# hybrid.net
KiCad netlist of a schematic drawn in EAGLE
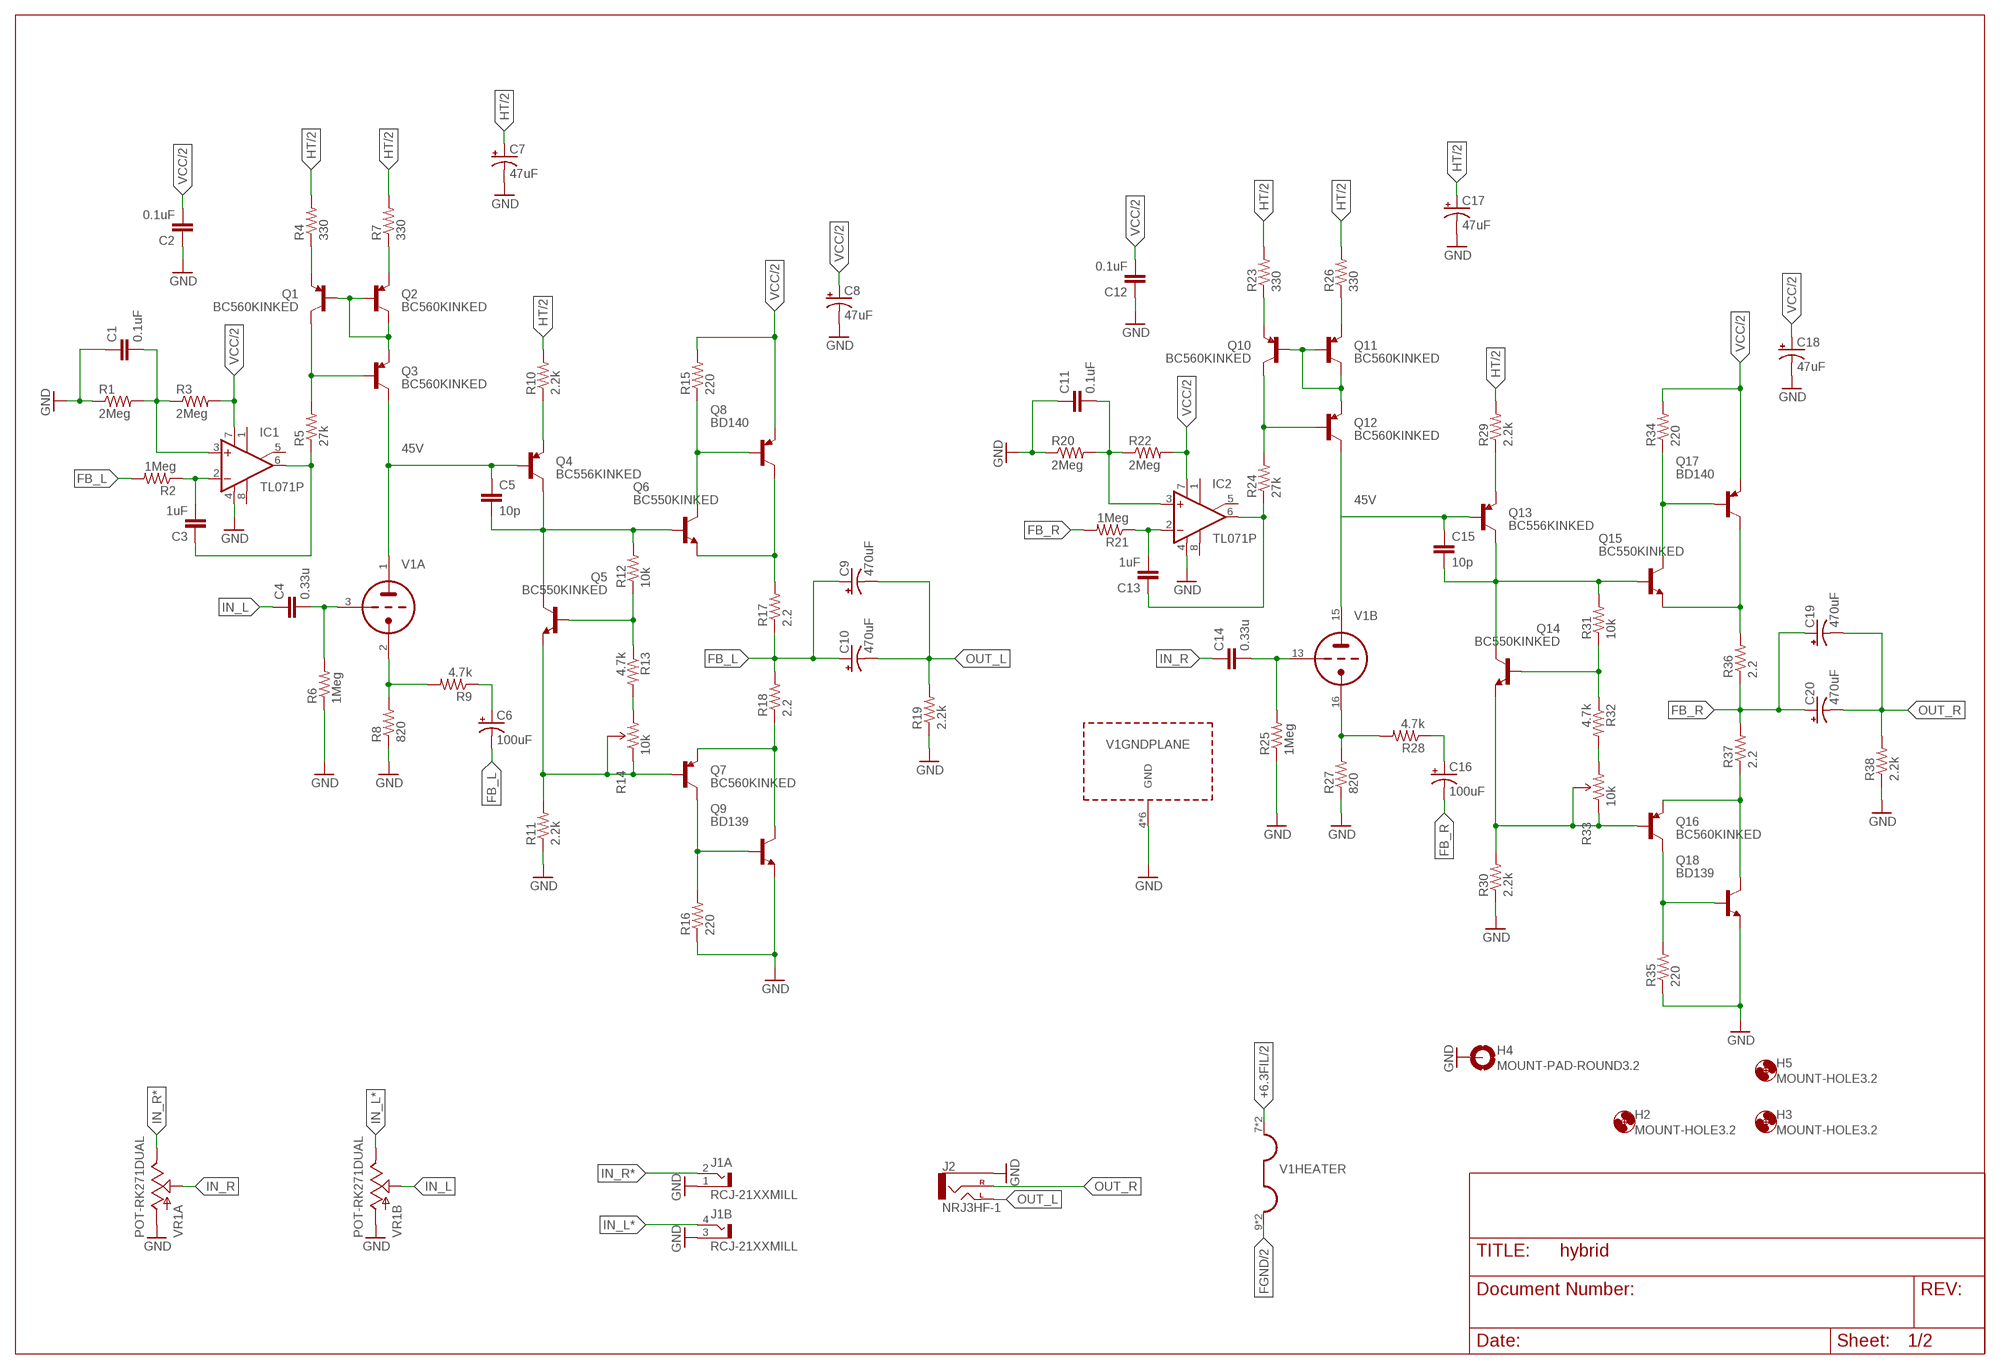
[diagram p0: schematic, sheet 1]
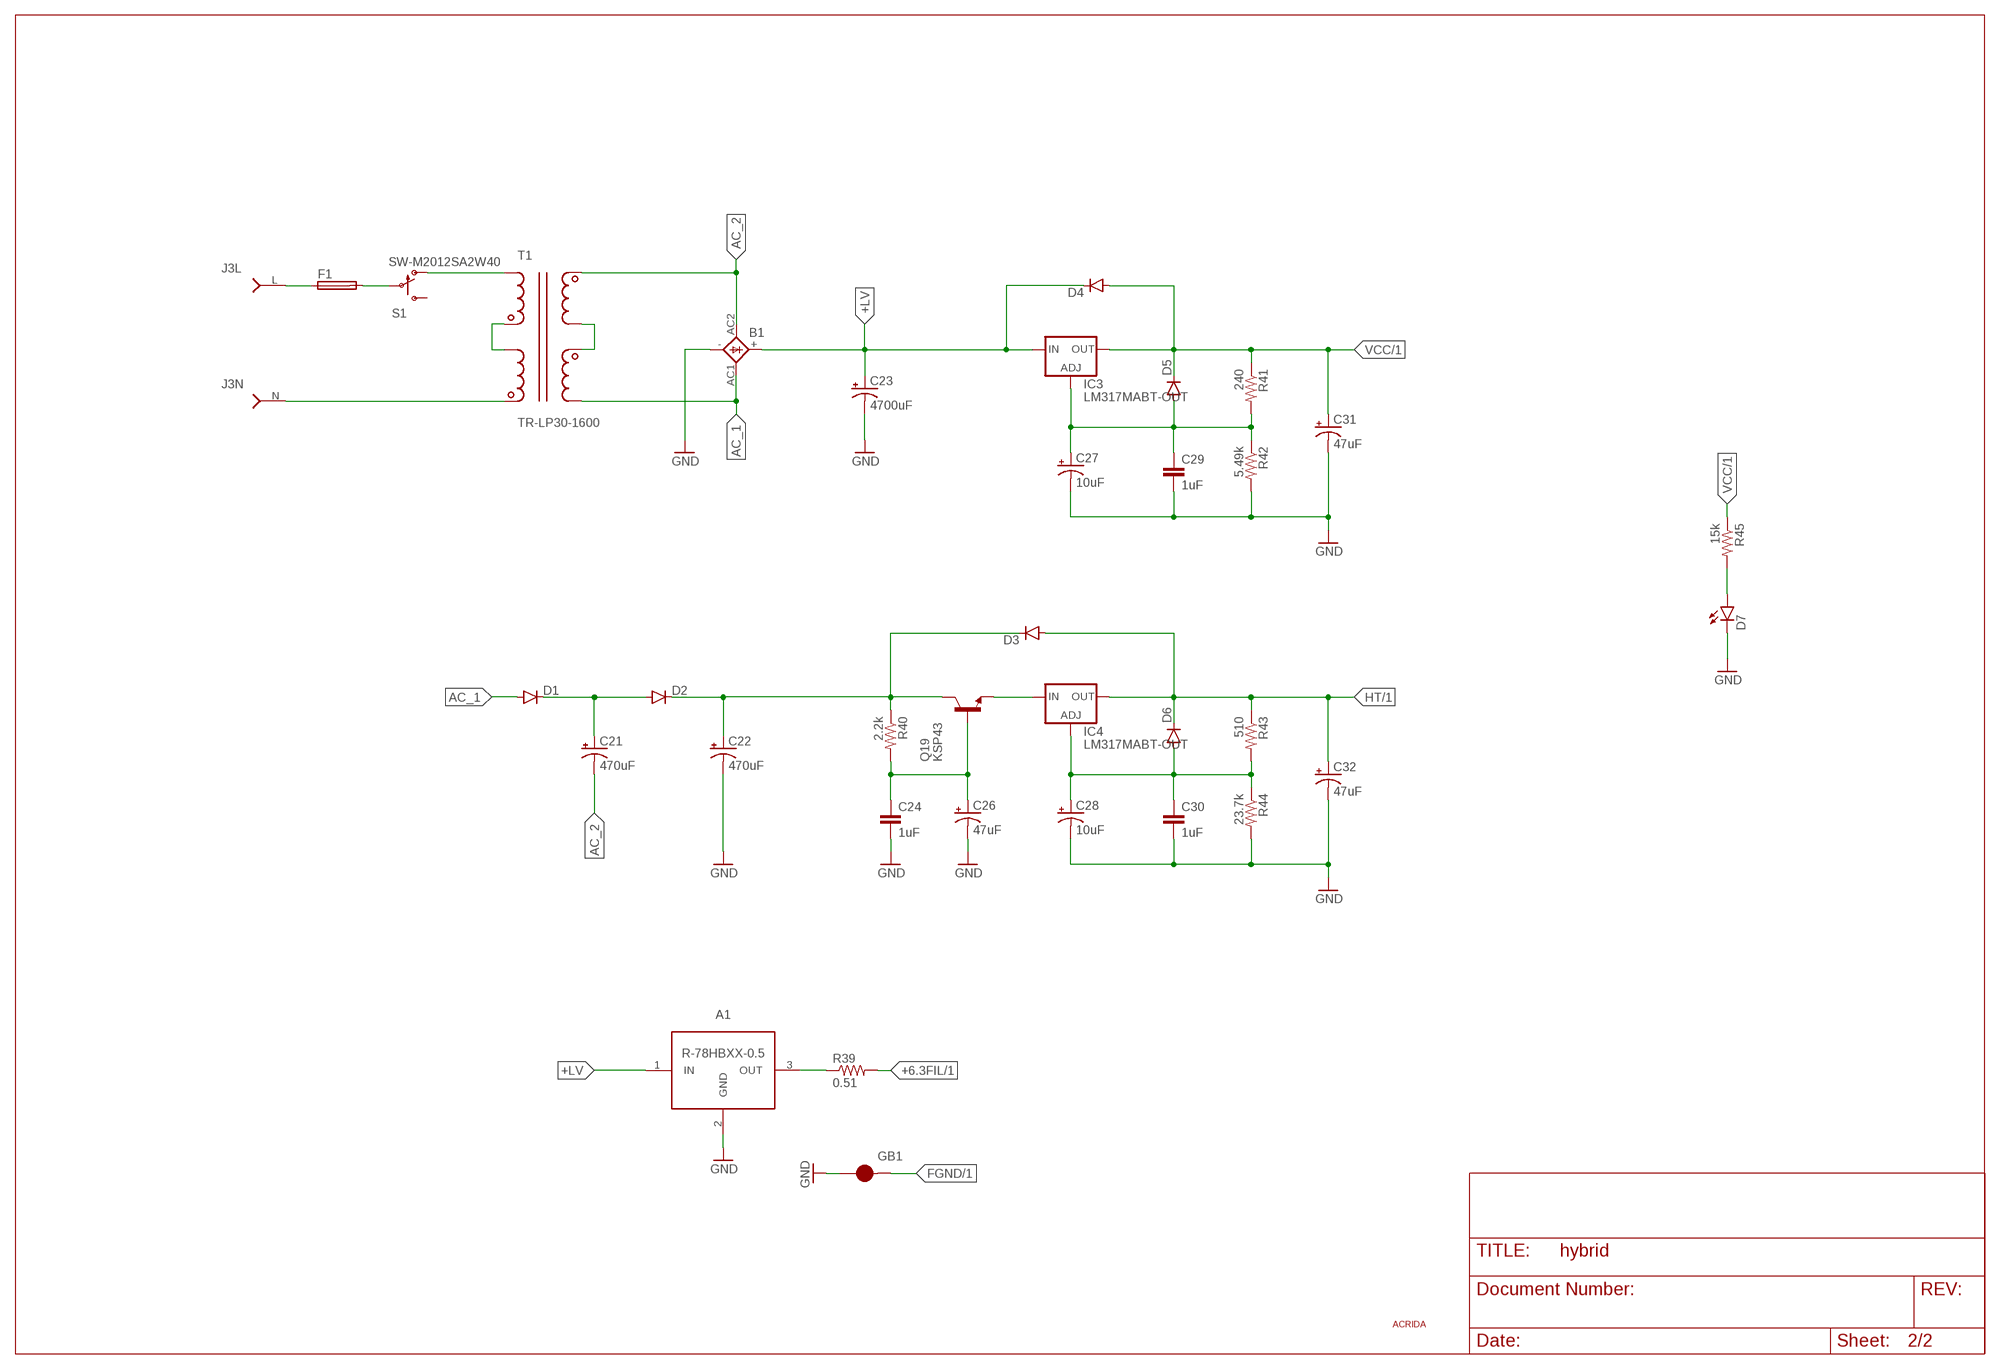
[diagram p1: schematic, sheet 2]

(export (version "E")
  (design (tool "Eeschema 10.0.6"))
  (components
    (comp (ref "A1")
      (value "R-78HBXX-0.5")
      (footprint "eagle-import:R-78HB")
      (libsource (lib "eagle-import") (part "R-78HBXX-0.5"))
    )
    (comp (ref "B1")
      (value "GBU4")
      (footprint "eagle-import:GBU4S")
      (libsource (lib "eagle-import") (part "GBU4"))
    )
    (comp (ref "C21")
      (value "470uF")
      (footprint "eagle-import:CPOL-RADIAL-18_7.5")
      (libsource (lib "eagle-import") (part "CAP_POLPTH-18/7.5"))
    )
    (comp (ref "C22")
      (value "470uF")
      (footprint "eagle-import:CPOL-RADIAL-18_7.5")
      (libsource (lib "eagle-import") (part "CAP_POLPTH-18/7.5"))
    )
    (comp (ref "C23")
      (value "4700uF")
      (footprint "eagle-import:CPOL-SNAPIN-30_10")
      (libsource (lib "eagle-import") (part "CAP_POLSNAPIN-30/10"))
    )
    (comp (ref "C24")
      (value "1uF")
      (footprint "eagle-import:CAP-PTH-SMALL")
      (libsource (lib "eagle-import") (part "CAPPTH"))
    )
    (comp (ref "C26")
      (value "47uF")
      (footprint "eagle-import:CPOL-RADIAL-12_5")
      (libsource (lib "eagle-import") (part "CAP_POLPTH-12/5"))
    )
    (comp (ref "C27")
      (value "10uF")
      (footprint "eagle-import:CPOL-RADIAL-5_2.5")
      (libsource (lib "eagle-import") (part "CAP_POLPTH-5/2.5"))
    )
    (comp (ref "C28")
      (value "10uF")
      (footprint "eagle-import:CPOL-RADIAL-6.5_2.5")
      (libsource (lib "eagle-import") (part "CAP_POLPTH-6.5/2.5"))
    )
    (comp (ref "C29")
      (value "1uF")
      (footprint "eagle-import:CAP-PTH-SMALL")
      (libsource (lib "eagle-import") (part "CAPPTH"))
    )
    (comp (ref "C30")
      (value "1uF")
      (footprint "eagle-import:CAP-PTH-SMALL")
      (libsource (lib "eagle-import") (part "CAPPTH"))
    )
    (comp (ref "C31")
      (value "47uF")
      (footprint "eagle-import:CPOL-RADIAL-8_3.5")
      (libsource (lib "eagle-import") (part "CAP_POLPTH-8/3.5"))
    )
    (comp (ref "C32")
      (value "47uF")
      (footprint "eagle-import:CPOL-RADIAL-8_3.5")
      (libsource (lib "eagle-import") (part "CAP_POLPTH-8/3.5"))
    )
    (comp (ref "D1")
      (value "DIODEPTH")
      (footprint "eagle-import:DIODE-1N4001")
      (libsource (lib "eagle-import") (part "DIODEPTH"))
    )
    (comp (ref "D2")
      (value "DIODEPTH")
      (footprint "eagle-import:DIODE-1N4001")
      (libsource (lib "eagle-import") (part "DIODEPTH"))
    )
    (comp (ref "D3")
      (value "DIODEPTH")
      (footprint "eagle-import:DIODE-1N4001")
      (libsource (lib "eagle-import") (part "DIODEPTH"))
    )
    (comp (ref "D4")
      (value "DIODEPTH")
      (footprint "eagle-import:DIODE-1N4001")
      (libsource (lib "eagle-import") (part "DIODEPTH"))
    )
    (comp (ref "D5")
      (value "DIODEPTH")
      (footprint "eagle-import:DIODE-1N4001")
      (libsource (lib "eagle-import") (part "DIODEPTH"))
    )
    (comp (ref "D6")
      (value "DIODEPTH")
      (footprint "eagle-import:DIODE-1N4001")
      (libsource (lib "eagle-import") (part "DIODEPTH"))
    )
    (comp (ref "D7")
      (value "LED3MM")
      (footprint "eagle-import:LED3MM")
      (libsource (lib "eagle-import") (part "LED3MM"))
    )
    (comp (ref "F1")
      (value "SH22,5")
      (footprint "eagle-import:SH22,5")
      (fields (field (name "MF") "SCHURTER") (field (name "MPN") "0031.8201"))
      (libsource (lib "eagle-import") (part "SH22,5"))
    )
    (comp (ref "GB1")
      (value "COPPER-BRIDGESM")
      (footprint "eagle-import:COPPER-BRIDGE-SM")
      (libsource (lib "eagle-import") (part "COPPER-BRIDGESM"))
    )
    (comp (ref "IC3")
      (value "LM317MABT-OUT")
      (footprint "eagle-import:TO220L1-OUT")
      (libsource (lib "eagle-import") (part "LM317?MABT-OUT"))
    )
    (comp (ref "IC4")
      (value "LM317MABT-OUT")
      (footprint "eagle-import:TO220L1-OUT")
      (libsource (lib "eagle-import") (part "LM317?MABT-OUT"))
    )
    (comp (ref "J3")
      (value "703W-00/54")
      (footprint "eagle-import:703W-00_54")
      (libsource (lib "eagle-import") (part "703W-00/54"))
    )
    (comp (ref "Q19")
      (value "KSP43")
      (footprint "eagle-import:TO-92")
      (libsource (lib "eagle-import") (part "KSP43"))
    )
    (comp (ref "R39")
      (value "0.51")
      (footprint "eagle-import:AXIAL-0.5")
      (libsource (lib "eagle-import") (part "my-res_RESISTORPTH-1/2W"))
    )
    (comp (ref "R40")
      (value "2.2k")
      (footprint "eagle-import:AXIAL-0.4")
      (libsource (lib "eagle-import") (part "RESISTORPTH-1/4W"))
    )
    (comp (ref "R41")
      (value "240")
      (footprint "eagle-import:AXIAL-0.4")
      (libsource (lib "eagle-import") (part "RESISTORPTH-1/4W"))
    )
    (comp (ref "R42")
      (value "5.49k")
      (footprint "eagle-import:AXIAL-0.4")
      (libsource (lib "eagle-import") (part "RESISTORPTH-1/4W"))
    )
    (comp (ref "R43")
      (value "510")
      (footprint "eagle-import:AXIAL-0.4")
      (libsource (lib "eagle-import") (part "RESISTORPTH-1/4W"))
    )
    (comp (ref "R44")
      (value "23.7k")
      (footprint "eagle-import:AXIAL-0.4")
      (libsource (lib "eagle-import") (part "RESISTORPTH-1/4W"))
    )
    (comp (ref "R45")
      (value "15k")
      (footprint "eagle-import:AXIAL-0.4")
      (libsource (lib "eagle-import") (part "RESISTORPTH-1/4W"))
    )
    (comp (ref "S1")
      (value "SW-M2012SA2W40")
      (footprint "eagle-import:SW-M2012S2A2G40")
      (libsource (lib "eagle-import") (part "SW-M2012SA2W40"))
    )
    (comp (ref "T1")
      (value "TR-LP30-1600")
      (footprint "eagle-import:TR-LP30-1600")
      (libsource (lib "eagle-import") (part "TR-LP30-1600"))
    )
    (comp (ref "U$1")
      (value "ACRIDA-LOGO")
      (footprint "eagle-import:ACRIDA-LOGO")
      (libsource (lib "eagle-import") (part "ACRIDA-LOGO"))
    )
    (comp (ref "C1")
      (value "0.1uF")
      (footprint "eagle-import:CAP-PTH-SMALL")
      (libsource (lib "eagle-import") (part "CAPPTH"))
    )
    (comp (ref "C2")
      (value "0.1uF")
      (footprint "eagle-import:CAP-PTH-SMALL")
      (libsource (lib "eagle-import") (part "CAPPTH"))
    )
    (comp (ref "C3")
      (value "1uF")
      (footprint "eagle-import:C5B5")
      (libsource (lib "eagle-import") (part "C5/5"))
    )
    (comp (ref "C4")
      (value "0.33u")
      (footprint "eagle-import:C5B3.5")
      (libsource (lib "eagle-import") (part "C5/3.5"))
    )
    (comp (ref "C5")
      (value "10p")
      (footprint "eagle-import:CAP-PTH-SMALL")
      (libsource (lib "eagle-import") (part "CAPPTH"))
    )
    (comp (ref "C6")
      (value "100uF")
      (footprint "eagle-import:CPOL-RADIAL-8_3.5")
      (libsource (lib "eagle-import") (part "CAP_POLPTH-8/3.5"))
    )
    (comp (ref "C7")
      (value "47uF")
      (footprint "eagle-import:CPOL-RADIAL-8_3.5")
      (libsource (lib "eagle-import") (part "CAP_POLPTH-8/3.5"))
    )
    (comp (ref "C8")
      (value "47uF")
      (footprint "eagle-import:CPOL-RADIAL-8_3.5")
      (libsource (lib "eagle-import") (part "CAP_POLPTH-8/3.5"))
    )
    (comp (ref "C9")
      (value "470uF")
      (footprint "eagle-import:CPOL-RADIAL-12.5_5")
      (libsource (lib "eagle-import") (part "CAP_POLPTH-12.5/5"))
    )
    (comp (ref "C10")
      (value "470uF")
      (footprint "eagle-import:CPOL-RADIAL-12.5_5")
      (libsource (lib "eagle-import") (part "CAP_POLPTH-12.5/5"))
    )
    (comp (ref "C11")
      (value "0.1uF")
      (footprint "eagle-import:CAP-PTH-SMALL")
      (libsource (lib "eagle-import") (part "CAPPTH"))
    )
    (comp (ref "C12")
      (value "0.1uF")
      (footprint "eagle-import:CAP-PTH-SMALL")
      (libsource (lib "eagle-import") (part "CAPPTH"))
    )
    (comp (ref "C13")
      (value "1uF")
      (footprint "eagle-import:C5B5")
      (libsource (lib "eagle-import") (part "C5/5"))
    )
    (comp (ref "C14")
      (value "0.33u")
      (footprint "eagle-import:C5B3.5")
      (libsource (lib "eagle-import") (part "C5/3.5"))
    )
    (comp (ref "C15")
      (value "10p")
      (footprint "eagle-import:CAP-PTH-SMALL")
      (libsource (lib "eagle-import") (part "CAPPTH"))
    )
    (comp (ref "C16")
      (value "100uF")
      (footprint "eagle-import:CPOL-RADIAL-8_3.5")
      (libsource (lib "eagle-import") (part "CAP_POLPTH-8/3.5"))
    )
    (comp (ref "C17")
      (value "47uF")
      (footprint "eagle-import:CPOL-RADIAL-8_3.5")
      (libsource (lib "eagle-import") (part "CAP_POLPTH-8/3.5"))
    )
    (comp (ref "C18")
      (value "47uF")
      (footprint "eagle-import:CPOL-RADIAL-8_3.5")
      (libsource (lib "eagle-import") (part "CAP_POLPTH-8/3.5"))
    )
    (comp (ref "C19")
      (value "470uF")
      (footprint "eagle-import:CPOL-RADIAL-12.5_5")
      (libsource (lib "eagle-import") (part "CAP_POLPTH-12.5/5"))
    )
    (comp (ref "C20")
      (value "470uF")
      (footprint "eagle-import:CPOL-RADIAL-12.5_5")
      (libsource (lib "eagle-import") (part "CAP_POLPTH-12.5/5"))
    )
    (comp (ref "H2")
      (value "MOUNT-HOLE3.2")
      (footprint "eagle-import:3,2")
      (libsource (lib "eagle-import") (part "MOUNT-HOLE3.2"))
    )
    (comp (ref "H3")
      (value "MOUNT-HOLE3.2")
      (footprint "eagle-import:3,2")
      (libsource (lib "eagle-import") (part "MOUNT-HOLE3.2"))
    )
    (comp (ref "H4")
      (value "MOUNT-PAD-ROUND3.2")
      (footprint "eagle-import:3,2-PAD")
      (libsource (lib "eagle-import") (part "MOUNT-PAD-ROUND3.2"))
    )
    (comp (ref "H5")
      (value "MOUNT-HOLE3.2")
      (footprint "eagle-import:3,2")
      (libsource (lib "eagle-import") (part "MOUNT-HOLE3.2"))
    )
    (comp (ref "IC1")
      (value "TL071P")
      (footprint "eagle-import:DIL08")
      (libsource (lib "eagle-import") (part "TL071P"))
    )
    (comp (ref "IC2")
      (value "TL071P")
      (footprint "eagle-import:DIL08")
      (libsource (lib "eagle-import") (part "TL071P"))
    )
    (comp (ref "J1")
      (value "RCJ-21XXMILL")
      (footprint "eagle-import:RCJ-21-MILL")
      (libsource (lib "eagle-import") (part "RCJ-21XXMILL"))
    )
    (comp (ref "J2")
      (value "NRJ3HF-1")
      (footprint "eagle-import:NRJ3HF")
      (libsource (lib "eagle-import") (part "NRJ3HF-1"))
    )
    (comp (ref "Q1")
      (value "BC560KINKED")
      (footprint "eagle-import:TO92-BENT")
      (libsource (lib "eagle-import") (part "BC560KINKED"))
    )
    (comp (ref "Q2")
      (value "BC560KINKED")
      (footprint "eagle-import:TO92-BENT")
      (libsource (lib "eagle-import") (part "BC560KINKED"))
    )
    (comp (ref "Q3")
      (value "BC560KINKED")
      (footprint "eagle-import:TO92-BENT")
      (libsource (lib "eagle-import") (part "BC560KINKED"))
    )
    (comp (ref "Q4")
      (value "BC556KINKED")
      (footprint "eagle-import:TO92-BENT")
      (libsource (lib "eagle-import") (part "BC556KINKED"))
    )
    (comp (ref "Q5")
      (value "BC550KINKED")
      (footprint "eagle-import:TO92-BENT")
      (libsource (lib "eagle-import") (part "BC550KINKED"))
    )
    (comp (ref "Q6")
      (value "BC550KINKED")
      (footprint "eagle-import:TO92-BENT")
      (libsource (lib "eagle-import") (part "BC550KINKED"))
    )
    (comp (ref "Q7")
      (value "BC560KINKED")
      (footprint "eagle-import:TO92-BENT")
      (libsource (lib "eagle-import") (part "BC560KINKED"))
    )
    (comp (ref "Q8")
      (value "BD140")
      (footprint "eagle-import:TO126")
      (libsource (lib "eagle-import") (part "BD140"))
    )
    (comp (ref "Q9")
      (value "BD139")
      (footprint "eagle-import:TO126")
      (libsource (lib "eagle-import") (part "BD139"))
    )
    (comp (ref "Q10")
      (value "BC560KINKED")
      (footprint "eagle-import:TO92-BENT")
      (libsource (lib "eagle-import") (part "BC560KINKED"))
    )
    (comp (ref "Q11")
      (value "BC560KINKED")
      (footprint "eagle-import:TO92-BENT")
      (libsource (lib "eagle-import") (part "BC560KINKED"))
    )
    (comp (ref "Q12")
      (value "BC560KINKED")
      (footprint "eagle-import:TO92-BENT")
      (libsource (lib "eagle-import") (part "BC560KINKED"))
    )
    (comp (ref "Q13")
      (value "BC556KINKED")
      (footprint "eagle-import:TO92-BENT")
      (libsource (lib "eagle-import") (part "BC556KINKED"))
    )
    (comp (ref "Q14")
      (value "BC550KINKED")
      (footprint "eagle-import:TO92-BENT")
      (libsource (lib "eagle-import") (part "BC550KINKED"))
    )
    (comp (ref "Q15")
      (value "BC550KINKED")
      (footprint "eagle-import:TO92-BENT")
      (libsource (lib "eagle-import") (part "BC550KINKED"))
    )
    (comp (ref "Q16")
      (value "BC560KINKED")
      (footprint "eagle-import:TO92-BENT")
      (libsource (lib "eagle-import") (part "BC560KINKED"))
    )
    (comp (ref "Q17")
      (value "BD140")
      (footprint "eagle-import:TO126")
      (libsource (lib "eagle-import") (part "BD140"))
    )
    (comp (ref "Q18")
      (value "BD139")
      (footprint "eagle-import:TO126")
      (libsource (lib "eagle-import") (part "BD139"))
    )
    (comp (ref "R1")
      (value "2Meg")
      (footprint "eagle-import:AXIAL-0.4")
      (libsource (lib "eagle-import") (part "RESISTORPTH-1/4W"))
    )
    (comp (ref "R2")
      (value "1Meg")
      (footprint "eagle-import:AXIAL-0.4")
      (libsource (lib "eagle-import") (part "RESISTORPTH-1/4W"))
    )
    (comp (ref "R3")
      (value "2Meg")
      (footprint "eagle-import:AXIAL-0.4")
      (libsource (lib "eagle-import") (part "RESISTORPTH-1/4W"))
    )
    (comp (ref "R4")
      (value "330")
      (footprint "eagle-import:AXIAL-0.4")
      (libsource (lib "eagle-import") (part "RESISTORPTH-1/4W"))
    )
    (comp (ref "R5")
      (value "27k")
      (footprint "eagle-import:AXIAL-0.4")
      (libsource (lib "eagle-import") (part "RESISTORPTH-1/4W"))
    )
    (comp (ref "R6")
      (value "1Meg")
      (footprint "eagle-import:AXIAL-0.4")
      (libsource (lib "eagle-import") (part "RESISTORPTH-1/4W"))
    )
    (comp (ref "R7")
      (value "330")
      (footprint "eagle-import:AXIAL-0.4")
      (libsource (lib "eagle-import") (part "RESISTORPTH-1/4W"))
    )
    (comp (ref "R8")
      (value "820")
      (footprint "eagle-import:AXIAL-0.4")
      (libsource (lib "eagle-import") (part "RESISTORPTH-1/4W"))
    )
    (comp (ref "R9")
      (value "4.7k")
      (footprint "eagle-import:AXIAL-0.4")
      (libsource (lib "eagle-import") (part "RESISTORPTH-1/4W"))
    )
    (comp (ref "R10")
      (value "2.2k")
      (footprint "eagle-import:AXIAL-0.4")
      (libsource (lib "eagle-import") (part "RESISTORPTH-1/4W"))
    )
    (comp (ref "R11")
      (value "2.2k")
      (footprint "eagle-import:AXIAL-0.4")
      (libsource (lib "eagle-import") (part "RESISTORPTH-1/4W"))
    )
    (comp (ref "R12")
      (value "10k")
      (footprint "eagle-import:AXIAL-0.4")
      (libsource (lib "eagle-import") (part "RESISTORPTH-1/4W"))
    )
    (comp (ref "R13")
      (value "4.7k")
      (footprint "eagle-import:AXIAL-0.4")
      (libsource (lib "eagle-import") (part "RESISTORPTH-1/4W"))
    )
    (comp (ref "R14")
      (value "10k")
      (footprint "eagle-import:3362U-2")
      (libsource (lib "eagle-import") (part "TRIMPOT3362U-2"))
    )
    (comp (ref "R15")
      (value "220")
      (footprint "eagle-import:AXIAL-0.4")
      (libsource (lib "eagle-import") (part "RESISTORPTH-1/4W"))
    )
    (comp (ref "R16")
      (value "220")
      (footprint "eagle-import:AXIAL-0.4")
      (libsource (lib "eagle-import") (part "RESISTORPTH-1/4W"))
    )
    (comp (ref "R17")
      (value "2.2")
      (footprint "eagle-import:AXIAL-0.4")
      (libsource (lib "eagle-import") (part "RESISTORPTH-1/4W"))
    )
    (comp (ref "R18")
      (value "2.2")
      (footprint "eagle-import:AXIAL-0.4")
      (libsource (lib "eagle-import") (part "RESISTORPTH-1/4W"))
    )
    (comp (ref "R19")
      (value "2.2k")
      (footprint "eagle-import:AXIAL-0.4")
      (libsource (lib "eagle-import") (part "RESISTORPTH-1/4W"))
    )
    (comp (ref "R20")
      (value "2Meg")
      (footprint "eagle-import:AXIAL-0.4")
      (libsource (lib "eagle-import") (part "RESISTORPTH-1/4W"))
    )
    (comp (ref "R21")
      (value "1Meg")
      (footprint "eagle-import:AXIAL-0.4")
      (libsource (lib "eagle-import") (part "RESISTORPTH-1/4W"))
    )
    (comp (ref "R22")
      (value "2Meg")
      (footprint "eagle-import:AXIAL-0.4")
      (libsource (lib "eagle-import") (part "RESISTORPTH-1/4W"))
    )
    (comp (ref "R23")
      (value "330")
      (footprint "eagle-import:AXIAL-0.4")
      (libsource (lib "eagle-import") (part "RESISTORPTH-1/4W"))
    )
    (comp (ref "R24")
      (value "27k")
      (footprint "eagle-import:AXIAL-0.4")
      (libsource (lib "eagle-import") (part "RESISTORPTH-1/4W"))
    )
    (comp (ref "R25")
      (value "1Meg")
      (footprint "eagle-import:AXIAL-0.4")
      (libsource (lib "eagle-import") (part "RESISTORPTH-1/4W"))
    )
    (comp (ref "R26")
      (value "330")
      (footprint "eagle-import:AXIAL-0.4")
      (libsource (lib "eagle-import") (part "RESISTORPTH-1/4W"))
    )
    (comp (ref "R27")
      (value "820")
      (footprint "eagle-import:AXIAL-0.4")
      (libsource (lib "eagle-import") (part "RESISTORPTH-1/4W"))
    )
    (comp (ref "R28")
      (value "4.7k")
      (footprint "eagle-import:AXIAL-0.4")
      (libsource (lib "eagle-import") (part "RESISTORPTH-1/4W"))
    )
    (comp (ref "R29")
      (value "2.2k")
      (footprint "eagle-import:AXIAL-0.4")
      (libsource (lib "eagle-import") (part "RESISTORPTH-1/4W"))
    )
    (comp (ref "R30")
      (value "2.2k")
      (footprint "eagle-import:AXIAL-0.4")
      (libsource (lib "eagle-import") (part "RESISTORPTH-1/4W"))
    )
    (comp (ref "R31")
      (value "10k")
      (footprint "eagle-import:AXIAL-0.4")
      (libsource (lib "eagle-import") (part "RESISTORPTH-1/4W"))
    )
    (comp (ref "R32")
      (value "4.7k")
      (footprint "eagle-import:AXIAL-0.4")
      (libsource (lib "eagle-import") (part "RESISTORPTH-1/4W"))
    )
    (comp (ref "R33")
      (value "10k")
      (footprint "eagle-import:3362U-2")
      (libsource (lib "eagle-import") (part "TRIMPOT3362U-2"))
    )
    (comp (ref "R34")
      (value "220")
      (footprint "eagle-import:AXIAL-0.4")
      (libsource (lib "eagle-import") (part "RESISTORPTH-1/4W"))
    )
    (comp (ref "R35")
      (value "220")
      (footprint "eagle-import:AXIAL-0.4")
      (libsource (lib "eagle-import") (part "RESISTORPTH-1/4W"))
    )
    (comp (ref "R36")
      (value "2.2")
      (footprint "eagle-import:AXIAL-0.4")
      (libsource (lib "eagle-import") (part "RESISTORPTH-1/4W"))
    )
    (comp (ref "R37")
      (value "2.2")
      (footprint "eagle-import:AXIAL-0.4")
      (libsource (lib "eagle-import") (part "RESISTORPTH-1/4W"))
    )
    (comp (ref "R38")
      (value "2.2k")
      (footprint "eagle-import:AXIAL-0.4")
      (libsource (lib "eagle-import") (part "RESISTORPTH-1/4W"))
    )
    (comp (ref "V1")
      (value "6DJ8-P-HORIZONTAL")
      (footprint "eagle-import:NOVAL-HORIZONTAL")
      (libsource (lib "eagle-import") (part "6DJ8-P-HORIZONTAL"))
    )
    (comp (ref "VR1")
      (value "POT-RK271DUAL")
      (footprint "eagle-import:RK271+PTD902")
      (libsource (lib "eagle-import") (part "POT-RK271DUAL"))
    )
  )
  (nets
    (net (code "1") (name "+6.3FIL") (class "Default")
      (node (ref "R39") (pin "P$2") (pinfunction "2_P$2") (pintype "passive"))
      (node (ref "V1") (pin "7") (pinfunction "H1_7") (pintype "passive"))
      (node (ref "V1") (pin "8") (pinfunction "H1_8") (pintype "passive"))
    )
    (net (code "2") (name "+LV") (class "Default")
      (node (ref "A1") (pin "1") (pinfunction "IN_1") (pintype "bidirectional"))
      (node (ref "B1") (pin "+") (pinfunction "+_+") (pintype "passive"))
      (node (ref "C23") (pin "1") (pinfunction "+_1") (pintype "passive"))
      (node (ref "D4") (pin "C") (pinfunction "C_C") (pintype "passive"))
      (node (ref "IC3") (pin "3") (pinfunction "IN_3") (pintype "input"))
    )
    (net (code "3") (name "AC_1") (class "Default")
      (node (ref "B1") (pin "AC1") (pinfunction "AC2_AC1") (pintype "passive"))
      (node (ref "D1") (pin "A") (pinfunction "A_A") (pintype "passive"))
      (node (ref "T1") (pin "8") (pinfunction "8_8") (pintype "bidirectional"))
    )
    (net (code "4") (name "AC_2") (class "Default")
      (node (ref "B1") (pin "AC2") (pinfunction "AC1_AC2") (pintype "passive"))
      (node (ref "C21") (pin "2") (pinfunction "-_2") (pintype "passive"))
      (node (ref "T1") (pin "5") (pinfunction "5_5") (pintype "bidirectional"))
    )
    (net (code "5") (name "FB_L") (class "Default")
      (node (ref "C10") (pin "+") (pinfunction "+_+") (pintype "passive"))
      (node (ref "C6") (pin "2") (pinfunction "-_2") (pintype "passive"))
      (node (ref "C9") (pin "+") (pinfunction "+_+") (pintype "passive"))
      (node (ref "R17") (pin "P$1") (pinfunction "1_P$1") (pintype "passive"))
      (node (ref "R18") (pin "P$2") (pinfunction "2_P$2") (pintype "passive"))
      (node (ref "R2") (pin "P$2") (pinfunction "2_P$2") (pintype "passive"))
    )
    (net (code "6") (name "FB_R") (class "Default")
      (node (ref "C16") (pin "2") (pinfunction "-_2") (pintype "passive"))
      (node (ref "C19") (pin "+") (pinfunction "+_+") (pintype "passive"))
      (node (ref "C20") (pin "+") (pinfunction "+_+") (pintype "passive"))
      (node (ref "R21") (pin "P$2") (pinfunction "2_P$2") (pintype "passive"))
      (node (ref "R36") (pin "P$1") (pinfunction "1_P$1") (pintype "passive"))
      (node (ref "R37") (pin "P$2") (pinfunction "2_P$2") (pintype "passive"))
    )
    (net (code "7") (name "FGND") (class "Default")
      (node (ref "GB1") (pin "2") (pinfunction "2_2") (pintype "passive"))
      (node (ref "V1") (pin "10") (pinfunction "H2_10") (pintype "passive"))
      (node (ref "V1") (pin "9") (pinfunction "H2_9") (pintype "passive"))
    )
    (net (code "8") (name "GND") (class "Default")
      (node (ref "A1") (pin "2") (pinfunction "GND_2") (pintype "bidirectional"))
      (node (ref "B1") (pin "-") (pinfunction "-_-") (pintype "passive"))
      (node (ref "C1") (pin "1") (pinfunction "1_1") (pintype "passive"))
      (node (ref "C11") (pin "1") (pinfunction "1_1") (pintype "passive"))
      (node (ref "C12") (pin "1") (pinfunction "1_1") (pintype "passive"))
      (node (ref "C17") (pin "2") (pinfunction "-_2") (pintype "passive"))
      (node (ref "C18") (pin "2") (pinfunction "-_2") (pintype "passive"))
      (node (ref "C2") (pin "1") (pinfunction "1_1") (pintype "passive"))
      (node (ref "C22") (pin "2") (pinfunction "-_2") (pintype "passive"))
      (node (ref "C23") (pin "2") (pinfunction "-_2") (pintype "passive"))
      (node (ref "C24") (pin "2") (pinfunction "2_2") (pintype "passive"))
      (node (ref "C26") (pin "-") (pinfunction "-_-") (pintype "passive"))
      (node (ref "C27") (pin "2") (pinfunction "-_2") (pintype "passive"))
      (node (ref "C28") (pin "2") (pinfunction "-_2") (pintype "passive"))
      (node (ref "C29") (pin "2") (pinfunction "2_2") (pintype "passive"))
      (node (ref "C30") (pin "2") (pinfunction "2_2") (pintype "passive"))
      (node (ref "C31") (pin "2") (pinfunction "-_2") (pintype "passive"))
      (node (ref "C32") (pin "2") (pinfunction "-_2") (pintype "passive"))
      (node (ref "C7") (pin "2") (pinfunction "-_2") (pintype "passive"))
      (node (ref "C8") (pin "2") (pinfunction "-_2") (pintype "passive"))
      (node (ref "D7") (pin "K") (pinfunction "C_K") (pintype "passive"))
      (node (ref "GB1") (pin "1") (pinfunction "1_1") (pintype "passive"))
      (node (ref "H4") (pin "B3,2") (pinfunction "MOUNT_B3,2") (pintype "passive"))
      (node (ref "IC1") (pin "4") (pinfunction "V-_4") (pintype "power_in"))
      (node (ref "IC2") (pin "4") (pinfunction "V-_4") (pintype "power_in"))
      (node (ref "J1") (pin "1") (pinfunction "S_1") (pintype "passive"))
      (node (ref "J1") (pin "3") (pinfunction "S_3") (pintype "passive"))
      (node (ref "J2") (pin "S") (pinfunction "SLEEVE_S") (pintype "bidirectional"))
      (node (ref "Q18") (pin "1") (pinfunction "E_1") (pintype "passive"))
      (node (ref "Q9") (pin "1") (pinfunction "E_1") (pintype "passive"))
      (node (ref "R1") (pin "P$1") (pinfunction "1_P$1") (pintype "passive"))
      (node (ref "R11") (pin "P$1") (pinfunction "1_P$1") (pintype "passive"))
      (node (ref "R16") (pin "P$1") (pinfunction "1_P$1") (pintype "passive"))
      (node (ref "R19") (pin "P$1") (pinfunction "1_P$1") (pintype "passive"))
      (node (ref "R20") (pin "P$1") (pinfunction "1_P$1") (pintype "passive"))
      (node (ref "R25") (pin "P$1") (pinfunction "1_P$1") (pintype "passive"))
      (node (ref "R27") (pin "P$1") (pinfunction "1_P$1") (pintype "passive"))
      (node (ref "R30") (pin "P$1") (pinfunction "1_P$1") (pintype "passive"))
      (node (ref "R35") (pin "P$1") (pinfunction "1_P$1") (pintype "passive"))
      (node (ref "R38") (pin "P$1") (pinfunction "1_P$1") (pintype "passive"))
      (node (ref "R42") (pin "P$2") (pinfunction "2_P$2") (pintype "passive"))
      (node (ref "R44") (pin "P$2") (pinfunction "2_P$2") (pintype "passive"))
      (node (ref "R6") (pin "P$1") (pinfunction "1_P$1") (pintype "passive"))
      (node (ref "R8") (pin "P$1") (pinfunction "1_P$1") (pintype "passive"))
      (node (ref "V1") (pin "11") (pinfunction "GND_11") (pintype "power_in"))
      (node (ref "V1") (pin "12") (pinfunction "GND_12") (pintype "power_in"))
      (node (ref "V1") (pin "14") (pinfunction "GND_14") (pintype "power_in"))
      (node (ref "V1") (pin "4") (pinfunction "GND_4") (pintype "power_in"))
      (node (ref "V1") (pin "5") (pinfunction "GND_5") (pintype "power_in"))
      (node (ref "V1") (pin "6") (pinfunction "GND_6") (pintype "power_in"))
      (node (ref "VR1") (pin "1.1.1") (pinfunction "A_1.1.1") (pintype "passive"))
      (node (ref "VR1") (pin "1.1.2") (pinfunction "A_1.1.2") (pintype "passive"))
      (node (ref "VR1") (pin "2.1.1") (pinfunction "A_2.1.1") (pintype "passive"))
      (node (ref "VR1") (pin "2.1.2") (pinfunction "A_2.1.2") (pintype "passive"))
    )
    (net (code "9") (name "HT") (class "Default")
      (node (ref "C17") (pin "1") (pinfunction "+_1") (pintype "passive"))
      (node (ref "C32") (pin "1") (pinfunction "+_1") (pintype "passive"))
      (node (ref "C7") (pin "1") (pinfunction "+_1") (pintype "passive"))
      (node (ref "D3") (pin "A") (pinfunction "A_A") (pintype "passive"))
      (node (ref "D6") (pin "C") (pinfunction "C_C") (pintype "passive"))
      (node (ref "IC4") (pin "2") (pinfunction "OUT_2") (pintype "passive"))
      (node (ref "R10") (pin "P$2") (pinfunction "2_P$2") (pintype "passive"))
      (node (ref "R23") (pin "P$2") (pinfunction "2_P$2") (pintype "passive"))
      (node (ref "R26") (pin "P$2") (pinfunction "2_P$2") (pintype "passive"))
      (node (ref "R29") (pin "P$2") (pinfunction "2_P$2") (pintype "passive"))
      (node (ref "R4") (pin "P$2") (pinfunction "2_P$2") (pintype "passive"))
      (node (ref "R43") (pin "P$1") (pinfunction "1_P$1") (pintype "passive"))
      (node (ref "R7") (pin "P$2") (pinfunction "2_P$2") (pintype "passive"))
    )
    (net (code "10") (name "IN_L") (class "Default")
      (node (ref "C4") (pin "1") (pinfunction "1_1") (pintype "passive"))
      (node (ref "VR1") (pin "2.2.1") (pinfunction "S_2.2.1") (pintype "passive"))
      (node (ref "VR1") (pin "2.2.2") (pinfunction "S_2.2.2") (pintype "passive"))
    )
    (net (code "11") (name "IN_L*") (class "Default")
      (node (ref "J1") (pin "4") (pinfunction "T_4") (pintype "passive"))
      (node (ref "VR1") (pin "2.3.1") (pinfunction "E_2.3.1") (pintype "passive"))
      (node (ref "VR1") (pin "2.3.2") (pinfunction "E_2.3.2") (pintype "passive"))
    )
    (net (code "12") (name "IN_R") (class "Default")
      (node (ref "C14") (pin "1") (pinfunction "1_1") (pintype "passive"))
      (node (ref "VR1") (pin "1.2") (pinfunction "S_1.2") (pintype "passive"))
    )
    (net (code "13") (name "IN_R*") (class "Default")
      (node (ref "J1") (pin "2") (pinfunction "T_2") (pintype "passive"))
      (node (ref "VR1") (pin "1.3.1") (pinfunction "E_1.3.1") (pintype "passive"))
      (node (ref "VR1") (pin "1.3.2") (pinfunction "E_1.3.2") (pintype "passive"))
    )
    (net (code "14") (name "Net-(A1-OUT)") (class "Default")
      (node (ref "A1") (pin "3") (pinfunction "OUT_3") (pintype "bidirectional"))
      (node (ref "R39") (pin "P$1") (pinfunction "1_P$1") (pintype "passive"))
    )
    (net (code "15") (name "Net-(C6-+)") (class "Default")
      (node (ref "C6") (pin "1") (pinfunction "+_1") (pintype "passive"))
      (node (ref "R9") (pin "P$1") (pinfunction "1_P$1") (pintype "passive"))
    )
    (net (code "16") (name "Net-(C16-+)") (class "Default")
      (node (ref "C16") (pin "1") (pinfunction "+_1") (pintype "passive"))
      (node (ref "R28") (pin "P$1") (pinfunction "1_P$1") (pintype "passive"))
    )
    (net (code "17") (name "Net-(C21-+)") (class "Default")
      (node (ref "C21") (pin "1") (pinfunction "+_1") (pintype "passive"))
      (node (ref "D1") (pin "C") (pinfunction "C_C") (pintype "passive"))
      (node (ref "D2") (pin "A") (pinfunction "A_A") (pintype "passive"))
    )
    (net (code "18") (name "Net-(C22-+)") (class "Default")
      (node (ref "C22") (pin "1") (pinfunction "+_1") (pintype "passive"))
      (node (ref "D2") (pin "C") (pinfunction "C_C") (pintype "passive"))
      (node (ref "D3") (pin "C") (pinfunction "C_C") (pintype "passive"))
      (node (ref "Q19") (pin "3") (pinfunction "C_3") (pintype "passive"))
      (node (ref "R40") (pin "P$1") (pinfunction "1_P$1") (pintype "passive"))
    )
    (net (code "19") (name "Net-(C27-+)") (class "Default")
      (node (ref "C27") (pin "1") (pinfunction "+_1") (pintype "passive"))
      (node (ref "C29") (pin "1") (pinfunction "1_1") (pintype "passive"))
      (node (ref "D5") (pin "A") (pinfunction "A_A") (pintype "passive"))
      (node (ref "IC3") (pin "1") (pinfunction "ADJ_1") (pintype "input"))
      (node (ref "R41") (pin "P$2") (pinfunction "2_P$2") (pintype "passive"))
      (node (ref "R42") (pin "P$1") (pinfunction "1_P$1") (pintype "passive"))
    )
    (net (code "20") (name "Net-(C28-+)") (class "Default")
      (node (ref "C28") (pin "1") (pinfunction "+_1") (pintype "passive"))
      (node (ref "C30") (pin "1") (pinfunction "1_1") (pintype "passive"))
      (node (ref "D6") (pin "A") (pinfunction "A_A") (pintype "passive"))
      (node (ref "IC4") (pin "1") (pinfunction "ADJ_1") (pintype "input"))
      (node (ref "R43") (pin "P$2") (pinfunction "2_P$2") (pintype "passive"))
      (node (ref "R44") (pin "P$1") (pinfunction "1_P$1") (pintype "passive"))
    )
    (net (code "21") (name "Net-(IC1-+IN)") (class "Default")
      (node (ref "C1") (pin "2") (pinfunction "2_2") (pintype "passive"))
      (node (ref "IC1") (pin "3") (pinfunction "+IN_3") (pintype "input"))
      (node (ref "R1") (pin "P$2") (pinfunction "2_P$2") (pintype "passive"))
      (node (ref "R3") (pin "P$1") (pinfunction "1_P$1") (pintype "passive"))
    )
    (net (code "22") (name "Net-(IC1--IN)") (class "Default")
      (node (ref "C3") (pin "2") (pinfunction "2_2") (pintype "passive"))
      (node (ref "IC1") (pin "2") (pinfunction "-IN_2") (pintype "input"))
      (node (ref "R2") (pin "P$1") (pinfunction "1_P$1") (pintype "passive"))
    )
    (net (code "23") (name "Net-(IC1-OUT)") (class "Default")
      (node (ref "C3") (pin "1") (pinfunction "1_1") (pintype "passive"))
      (node (ref "IC1") (pin "6") (pinfunction "OUT_6") (pintype "output"))
      (node (ref "R5") (pin "P$1") (pinfunction "1_P$1") (pintype "passive"))
    )
    (net (code "24") (name "Net-(IC2-+IN)") (class "Default")
      (node (ref "C11") (pin "2") (pinfunction "2_2") (pintype "passive"))
      (node (ref "IC2") (pin "3") (pinfunction "+IN_3") (pintype "input"))
      (node (ref "R20") (pin "P$2") (pinfunction "2_P$2") (pintype "passive"))
      (node (ref "R22") (pin "P$1") (pinfunction "1_P$1") (pintype "passive"))
    )
    (net (code "25") (name "Net-(IC2--IN)") (class "Default")
      (node (ref "C13") (pin "2") (pinfunction "2_2") (pintype "passive"))
      (node (ref "IC2") (pin "2") (pinfunction "-IN_2") (pintype "input"))
      (node (ref "R21") (pin "P$1") (pinfunction "1_P$1") (pintype "passive"))
    )
    (net (code "26") (name "Net-(IC2-OUT)") (class "Default")
      (node (ref "C13") (pin "1") (pinfunction "1_1") (pintype "passive"))
      (node (ref "IC2") (pin "6") (pinfunction "OUT_6") (pintype "output"))
      (node (ref "R24") (pin "P$1") (pinfunction "1_P$1") (pintype "passive"))
    )
    (net (code "27") (name "Net-(IC4-IN)") (class "Default")
      (node (ref "IC4") (pin "3") (pinfunction "IN_3") (pintype "input"))
      (node (ref "Q19") (pin "1") (pinfunction "E_1") (pintype "passive"))
    )
    (net (code "28") (name "Net-(J3B-P$1)") (class "Default")
      (node (ref "F1") (pin "1") (pinfunction "1_1") (pintype "passive"))
      (node (ref "J3") (pin "L") (pinfunction "P$1_L") (pintype "power_in"))
    )
    (net (code "29") (name "Net-(J3C-P$1)") (class "Default")
      (node (ref "J3") (pin "N") (pinfunction "P$1_N") (pintype "power_in"))
      (node (ref "T1") (pin "1") (pinfunction "1_1") (pintype "bidirectional"))
    )
    (net (code "30") (name "Net-(Q1-B)") (class "Default")
      (node (ref "Q1") (pin "2") (pinfunction "B_2") (pintype "passive"))
      (node (ref "Q2") (pin "1") (pinfunction "C_1") (pintype "passive"))
      (node (ref "Q2") (pin "2") (pinfunction "B_2") (pintype "passive"))
      (node (ref "Q3") (pin "3") (pinfunction "E_3") (pintype "passive"))
    )
    (net (code "31") (name "Net-(Q1-C)") (class "Default")
      (node (ref "Q1") (pin "1") (pinfunction "C_1") (pintype "passive"))
      (node (ref "Q3") (pin "2") (pinfunction "B_2") (pintype "passive"))
      (node (ref "R5") (pin "P$2") (pinfunction "2_P$2") (pintype "passive"))
    )
    (net (code "32") (name "Net-(Q1-E)") (class "Default")
      (node (ref "Q1") (pin "3") (pinfunction "E_3") (pintype "passive"))
      (node (ref "R4") (pin "P$1") (pinfunction "1_P$1") (pintype "passive"))
    )
    (net (code "33") (name "Net-(Q2-E)") (class "Default")
      (node (ref "Q2") (pin "3") (pinfunction "E_3") (pintype "passive"))
      (node (ref "R7") (pin "P$1") (pinfunction "1_P$1") (pintype "passive"))
    )
    (net (code "34") (name "Net-(Q3-C)") (class "Default")
      (node (ref "C5") (pin "1") (pinfunction "1_1") (pintype "passive"))
      (node (ref "Q3") (pin "1") (pinfunction "C_1") (pintype "passive"))
      (node (ref "Q4") (pin "2") (pinfunction "B_2") (pintype "passive"))
      (node (ref "V1") (pin "1") (pinfunction "TA_1") (pintype "passive"))
    )
    (net (code "35") (name "Net-(Q4-C)") (class "Default")
      (node (ref "C5") (pin "2") (pinfunction "2_2") (pintype "passive"))
      (node (ref "Q4") (pin "1") (pinfunction "C_1") (pintype "passive"))
      (node (ref "Q5") (pin "1") (pinfunction "C_1") (pintype "passive"))
      (node (ref "Q6") (pin "2") (pinfunction "B_2") (pintype "passive"))
      (node (ref "R12") (pin "P$2") (pinfunction "2_P$2") (pintype "passive"))
    )
    (net (code "36") (name "Net-(Q4-E)") (class "Default")
      (node (ref "Q4") (pin "3") (pinfunction "E_3") (pintype "passive"))
      (node (ref "R10") (pin "P$1") (pinfunction "1_P$1") (pintype "passive"))
    )
    (net (code "37") (name "Net-(Q5-B)") (class "Default")
      (node (ref "Q5") (pin "2") (pinfunction "B_2") (pintype "passive"))
      (node (ref "R12") (pin "P$1") (pinfunction "1_P$1") (pintype "passive"))
      (node (ref "R13") (pin "P$1") (pinfunction "1_P$1") (pintype "passive"))
    )
    (net (code "38") (name "Net-(Q5-E)") (class "Default")
      (node (ref "Q5") (pin "3") (pinfunction "E_3") (pintype "passive"))
      (node (ref "Q7") (pin "2") (pinfunction "B_2") (pintype "passive"))
      (node (ref "R11") (pin "P$2") (pinfunction "2_P$2") (pintype "passive"))
      (node (ref "R14") (pin "1") (pinfunction "CCW_1") (pintype "passive"))
      (node (ref "R14") (pin "2") (pinfunction "WIPER_2") (pintype "passive"))
    )
    (net (code "39") (name "Net-(Q6-C)") (class "Default")
      (node (ref "Q6") (pin "1") (pinfunction "C_1") (pintype "passive"))
      (node (ref "Q8") (pin "3") (pinfunction "B_3") (pintype "passive"))
      (node (ref "R15") (pin "P$1") (pinfunction "1_P$1") (pintype "passive"))
    )
    (net (code "40") (name "Net-(Q6-E)") (class "Default")
      (node (ref "Q6") (pin "3") (pinfunction "E_3") (pintype "passive"))
      (node (ref "Q8") (pin "2") (pinfunction "C_2") (pintype "passive"))
      (node (ref "R17") (pin "P$2") (pinfunction "2_P$2") (pintype "passive"))
    )
    (net (code "41") (name "Net-(Q7-C)") (class "Default")
      (node (ref "Q7") (pin "1") (pinfunction "C_1") (pintype "passive"))
      (node (ref "Q9") (pin "3") (pinfunction "B_3") (pintype "passive"))
      (node (ref "R16") (pin "P$2") (pinfunction "2_P$2") (pintype "passive"))
    )
    (net (code "42") (name "Net-(Q7-E)") (class "Default")
      (node (ref "Q7") (pin "3") (pinfunction "E_3") (pintype "passive"))
      (node (ref "Q9") (pin "2") (pinfunction "C_2") (pintype "passive"))
      (node (ref "R18") (pin "P$1") (pinfunction "1_P$1") (pintype "passive"))
    )
    (net (code "43") (name "Net-(Q10-B)") (class "Default")
      (node (ref "Q10") (pin "2") (pinfunction "B_2") (pintype "passive"))
      (node (ref "Q11") (pin "1") (pinfunction "C_1") (pintype "passive"))
      (node (ref "Q11") (pin "2") (pinfunction "B_2") (pintype "passive"))
      (node (ref "Q12") (pin "3") (pinfunction "E_3") (pintype "passive"))
    )
    (net (code "44") (name "Net-(Q10-C)") (class "Default")
      (node (ref "Q10") (pin "1") (pinfunction "C_1") (pintype "passive"))
      (node (ref "Q12") (pin "2") (pinfunction "B_2") (pintype "passive"))
      (node (ref "R24") (pin "P$2") (pinfunction "2_P$2") (pintype "passive"))
    )
    (net (code "45") (name "Net-(Q10-E)") (class "Default")
      (node (ref "Q10") (pin "3") (pinfunction "E_3") (pintype "passive"))
      (node (ref "R23") (pin "P$1") (pinfunction "1_P$1") (pintype "passive"))
    )
    (net (code "46") (name "Net-(Q11-E)") (class "Default")
      (node (ref "Q11") (pin "3") (pinfunction "E_3") (pintype "passive"))
      (node (ref "R26") (pin "P$1") (pinfunction "1_P$1") (pintype "passive"))
    )
    (net (code "47") (name "Net-(Q13-C)") (class "Default")
      (node (ref "C15") (pin "2") (pinfunction "2_2") (pintype "passive"))
      (node (ref "Q13") (pin "1") (pinfunction "C_1") (pintype "passive"))
      (node (ref "Q14") (pin "1") (pinfunction "C_1") (pintype "passive"))
      (node (ref "Q15") (pin "2") (pinfunction "B_2") (pintype "passive"))
      (node (ref "R31") (pin "P$2") (pinfunction "2_P$2") (pintype "passive"))
    )
    (net (code "48") (name "Net-(Q13-E)") (class "Default")
      (node (ref "Q13") (pin "3") (pinfunction "E_3") (pintype "passive"))
      (node (ref "R29") (pin "P$1") (pinfunction "1_P$1") (pintype "passive"))
    )
    (net (code "49") (name "Net-(Q14-B)") (class "Default")
      (node (ref "Q14") (pin "2") (pinfunction "B_2") (pintype "passive"))
      (node (ref "R31") (pin "P$1") (pinfunction "1_P$1") (pintype "passive"))
      (node (ref "R32") (pin "P$1") (pinfunction "1_P$1") (pintype "passive"))
    )
    (net (code "50") (name "Net-(Q14-E)") (class "Default")
      (node (ref "Q14") (pin "3") (pinfunction "E_3") (pintype "passive"))
      (node (ref "Q16") (pin "2") (pinfunction "B_2") (pintype "passive"))
      (node (ref "R30") (pin "P$2") (pinfunction "2_P$2") (pintype "passive"))
      (node (ref "R33") (pin "1") (pinfunction "CCW_1") (pintype "passive"))
      (node (ref "R33") (pin "2") (pinfunction "WIPER_2") (pintype "passive"))
    )
    (net (code "51") (name "Net-(Q15-C)") (class "Default")
      (node (ref "Q15") (pin "1") (pinfunction "C_1") (pintype "passive"))
      (node (ref "Q17") (pin "3") (pinfunction "B_3") (pintype "passive"))
      (node (ref "R34") (pin "P$1") (pinfunction "1_P$1") (pintype "passive"))
    )
    (net (code "52") (name "Net-(Q15-E)") (class "Default")
      (node (ref "Q15") (pin "3") (pinfunction "E_3") (pintype "passive"))
      (node (ref "Q17") (pin "2") (pinfunction "C_2") (pintype "passive"))
      (node (ref "R36") (pin "P$2") (pinfunction "2_P$2") (pintype "passive"))
    )
    (net (code "53") (name "Net-(Q16-C)") (class "Default")
      (node (ref "Q16") (pin "1") (pinfunction "C_1") (pintype "passive"))
      (node (ref "Q18") (pin "3") (pinfunction "B_3") (pintype "passive"))
      (node (ref "R35") (pin "P$2") (pinfunction "2_P$2") (pintype "passive"))
    )
    (net (code "54") (name "Net-(Q16-E)") (class "Default")
      (node (ref "Q16") (pin "3") (pinfunction "E_3") (pintype "passive"))
      (node (ref "Q18") (pin "2") (pinfunction "C_2") (pintype "passive"))
      (node (ref "R37") (pin "P$1") (pinfunction "1_P$1") (pintype "passive"))
    )
    (net (code "55") (name "Net-(Q19-B)") (class "Default")
      (node (ref "C24") (pin "1") (pinfunction "1_1") (pintype "passive"))
      (node (ref "C26") (pin "+") (pinfunction "+_+") (pintype "passive"))
      (node (ref "Q19") (pin "2") (pinfunction "B_2") (pintype "passive"))
      (node (ref "R40") (pin "P$2") (pinfunction "2_P$2") (pintype "passive"))
    )
    (net (code "56") (name "Net-(R6-2)") (class "Default")
      (node (ref "C4") (pin "2") (pinfunction "2_2") (pintype "passive"))
      (node (ref "R6") (pin "P$2") (pinfunction "2_P$2") (pintype "passive"))
      (node (ref "V1") (pin "3") (pinfunction "TG_3") (pintype "passive"))
    )
    (net (code "57") (name "Net-(R8-2)") (class "Default")
      (node (ref "R8") (pin "P$2") (pinfunction "2_P$2") (pintype "passive"))
      (node (ref "R9") (pin "P$2") (pinfunction "2_P$2") (pintype "passive"))
      (node (ref "V1") (pin "2") (pinfunction "TK_2") (pintype "passive"))
    )
    (net (code "58") (name "Net-(R13-2)") (class "Default")
      (node (ref "R13") (pin "P$2") (pinfunction "2_P$2") (pintype "passive"))
      (node (ref "R14") (pin "3") (pinfunction "CW_3") (pintype "passive"))
    )
    (net (code "59") (name "Net-(R25-2)") (class "Default")
      (node (ref "C14") (pin "2") (pinfunction "2_2") (pintype "passive"))
      (node (ref "R25") (pin "P$2") (pinfunction "2_P$2") (pintype "passive"))
      (node (ref "V1") (pin "13") (pinfunction "TG_13") (pintype "passive"))
    )
    (net (code "60") (name "Net-(R27-2)") (class "Default")
      (node (ref "R27") (pin "P$2") (pinfunction "2_P$2") (pintype "passive"))
      (node (ref "R28") (pin "P$2") (pinfunction "2_P$2") (pintype "passive"))
      (node (ref "V1") (pin "16") (pinfunction "TK_16") (pintype "passive"))
    )
    (net (code "61") (name "Net-(R32-2)") (class "Default")
      (node (ref "R32") (pin "P$2") (pinfunction "2_P$2") (pintype "passive"))
      (node (ref "R33") (pin "3") (pinfunction "CW_3") (pintype "passive"))
    )
    (net (code "62") (name "Net-(R45-2)") (class "Default")
      (node (ref "D7") (pin "A") (pinfunction "A_A") (pintype "passive"))
      (node (ref "R45") (pin "P$2") (pinfunction "2_P$2") (pintype "passive"))
    )
    (net (code "63") (name "Net-(S1-O)") (class "Default")
      (node (ref "S1") (pin "UP-CONNECT") (pinfunction "O_UP-CONNECT") (pintype "passive"))
      (node (ref "T1") (pin "4") (pinfunction "4_4") (pintype "bidirectional"))
    )
    (net (code "64") (name "Net-(S1-P)") (class "Default")
      (node (ref "F1") (pin "2") (pinfunction "2_2") (pintype "passive"))
      (node (ref "S1") (pin "S") (pinfunction "P_S") (pintype "passive"))
    )
    (net (code "65") (name "Net-(T1-Pad2)") (class "Default")
      (node (ref "T1") (pin "2") (pinfunction "2_2") (pintype "bidirectional"))
      (node (ref "T1") (pin "3") (pinfunction "3_3") (pintype "bidirectional"))
    )
    (net (code "66") (name "Net-(T1-Pad6)") (class "Default")
      (node (ref "T1") (pin "6") (pinfunction "6_6") (pintype "bidirectional"))
      (node (ref "T1") (pin "7") (pinfunction "7_7") (pintype "bidirectional"))
    )
    (net (code "67") (name "OUT_L") (class "Default")
      (node (ref "C10") (pin "-") (pinfunction "-_-") (pintype "passive"))
      (node (ref "C9") (pin "-") (pinfunction "-_-") (pintype "passive"))
      (node (ref "J2") (pin "T") (pinfunction "LEFT_T") (pintype "bidirectional"))
      (node (ref "R19") (pin "P$2") (pinfunction "2_P$2") (pintype "passive"))
    )
    (net (code "68") (name "OUT_R") (class "Default")
      (node (ref "C19") (pin "-") (pinfunction "-_-") (pintype "passive"))
      (node (ref "C20") (pin "-") (pinfunction "-_-") (pintype "passive"))
      (node (ref "J2") (pin "R") (pinfunction "RIGHT_R") (pintype "bidirectional"))
      (node (ref "R38") (pin "P$2") (pinfunction "2_P$2") (pintype "passive"))
    )
    (net (code "69") (name "PL_R") (class "Default")
      (node (ref "C15") (pin "1") (pinfunction "1_1") (pintype "passive"))
      (node (ref "Q12") (pin "1") (pinfunction "C_1") (pintype "passive"))
      (node (ref "Q13") (pin "2") (pinfunction "B_2") (pintype "passive"))
      (node (ref "V1") (pin "15") (pinfunction "TA_15") (pintype "passive"))
    )
    (net (code "70") (name "VCC") (class "Default")
      (node (ref "C12") (pin "2") (pinfunction "2_2") (pintype "passive"))
      (node (ref "C18") (pin "1") (pinfunction "+_1") (pintype "passive"))
      (node (ref "C2") (pin "2") (pinfunction "2_2") (pintype "passive"))
      (node (ref "C31") (pin "1") (pinfunction "+_1") (pintype "passive"))
      (node (ref "C8") (pin "1") (pinfunction "+_1") (pintype "passive"))
      (node (ref "D4") (pin "A") (pinfunction "A_A") (pintype "passive"))
      (node (ref "D5") (pin "C") (pinfunction "C_C") (pintype "passive"))
      (node (ref "IC1") (pin "7") (pinfunction "V+_7") (pintype "power_in"))
      (node (ref "IC2") (pin "7") (pinfunction "V+_7") (pintype "power_in"))
      (node (ref "IC3") (pin "2") (pinfunction "OUT_2") (pintype "passive"))
      (node (ref "Q17") (pin "1") (pinfunction "E_1") (pintype "passive"))
      (node (ref "Q8") (pin "1") (pinfunction "E_1") (pintype "passive"))
      (node (ref "R15") (pin "P$2") (pinfunction "2_P$2") (pintype "passive"))
      (node (ref "R22") (pin "P$2") (pinfunction "2_P$2") (pintype "passive"))
      (node (ref "R3") (pin "P$2") (pinfunction "2_P$2") (pintype "passive"))
      (node (ref "R34") (pin "P$2") (pinfunction "2_P$2") (pintype "passive"))
      (node (ref "R41") (pin "P$1") (pinfunction "1_P$1") (pintype "passive"))
      (node (ref "R45") (pin "P$1") (pinfunction "1_P$1") (pintype "passive"))
    )
    (net (code "71") (name "unconnected-(IC1-ON1-Pad1)") (class "Default")
      (node (ref "IC1") (pin "1") (pinfunction "ON1_1") (pintype "passive"))
    )
    (net (code "72") (name "unconnected-(IC1-ON2-Pad5)") (class "Default")
      (node (ref "IC1") (pin "5") (pinfunction "ON2_5") (pintype "passive"))
    )
    (net (code "73") (name "unconnected-(IC1-OPT-Pad8)") (class "Default")
      (node (ref "IC1") (pin "8") (pinfunction "OPT_8") (pintype "passive"))
    )
    (net (code "74") (name "unconnected-(IC2-ON1-Pad1)") (class "Default")
      (node (ref "IC2") (pin "1") (pinfunction "ON1_1") (pintype "passive"))
    )
    (net (code "75") (name "unconnected-(IC2-ON2-Pad5)") (class "Default")
      (node (ref "IC2") (pin "5") (pinfunction "ON2_5") (pintype "passive"))
    )
    (net (code "76") (name "unconnected-(IC2-OPT-Pad8)") (class "Default")
      (node (ref "IC2") (pin "8") (pinfunction "OPT_8") (pintype "passive"))
    )
    (net (code "77") (name "unconnected-(S1-S-PadDN-CONNECT)") (class "Default")
      (node (ref "S1") (pin "DN-CONNECT") (pinfunction "S_DN-CONNECT") (pintype "passive"))
    )
  )
)
